# DC_unit.net
KiCad netlist of a schematic drawn in Altium Designer
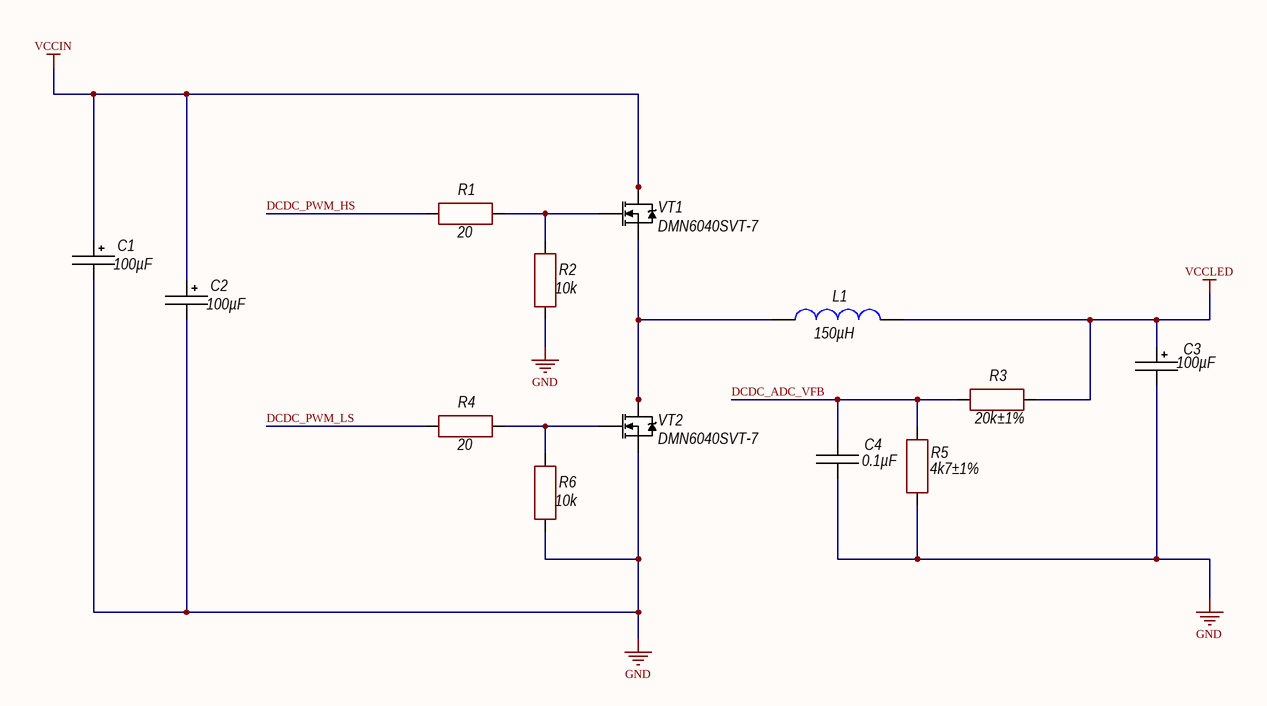
[diagram p0: DC unit.SchDoc]

(export (version "E")
  (design (tool "Eeschema 10.0.6"))
  (components
    (comp (ref "C1") (value "100µF") (footprint "D8C3.2H12") (libsource (lib "Discrete") (part "AlumCap")))
    (comp (ref "C2") (value "100µF") (footprint "D8C3.2H12") (libsource (lib "Discrete") (part "AlumCap")))
    (comp (ref "C3")
      (value "100µF")
      (footprint "TANTAL_D")
      (fields (field (name "MANUFACTURER") "Vishay Intertechnology Inc."))
      (libsource (lib "Discrete") (part "TantalCap"))
    )
    (comp (ref "C4") (value "0.1µF") (footprint "CH0603C") (libsource (lib "Discrete") (part "Capacitor")))
    (comp (ref "L1")
      (value "150µH")
      (footprint "IND: CDRH127")
      (fields (field (name "MANUFACTURER") "Sumida Electric"))
      (libsource (lib "Discrete") (part "Inductor"))
    )
    (comp (ref "R1") (value "20") (footprint "CH0603R") (libsource (lib "Discrete") (part "Resistor")))
    (comp (ref "R2") (value "10k") (footprint "CH0603R") (libsource (lib "") (part "Resistor_1")))
    (comp (ref "R3")
      (value "20k")
      (footprint "CH0603R")
      (fields (field (name "COMPONENTKIND") "±1%"))
      (libsource (lib "Discrete") (part "Resistor"))
    )
    (comp (ref "R4") (value "20") (footprint "CH0603R") (libsource (lib "Discrete") (part "Resistor")))
    (comp (ref "R5")
      (value "4k7")
      (footprint "CH0603R")
      (fields (field (name "COMPONENTKIND") "±1%"))
      (libsource (lib "") (part "Resistor_1"))
    )
    (comp (ref "R6") (value "10k") (footprint "CH0603R") (libsource (lib "") (part "Resistor_1")))
    (comp (ref "VT1")
      (value "DMN6040SVT-7")
      (footprint "TSOT23-6")
      (description "Mosfet")
      (fields (field (name "MANUFACTURER") "Diodes Incorporated"))
      (libsource (lib "Transistor") (part "DMN6040SVT-7"))
    )
    (comp (ref "VT2")
      (value "DMN6040SVT-7")
      (footprint "TSOT23-6")
      (description "Mosfet")
      (fields (field (name "MANUFACTURER") "Diodes Incorporated"))
      (libsource (lib "Transistor") (part "DMN6040SVT-7"))
    )
  )
  (nets
    (net (code "1") (name "/DCDC_ADC_VFB") (class "Default")
      (node (ref "C4") (pin "1") (pinfunction "1_1") (pintype "power_in"))
      (node (ref "R3") (pin "1") (pinfunction "1_1") (pintype "passive"))
      (node (ref "R5") (pin "2") (pinfunction "2_2") (pintype "passive"))
    )
    (net (code "2") (name "/DCDC_PWM_HS") (class "Default")
      (node (ref "R1") (pin "1") (pinfunction "1_1") (pintype "passive"))
    )
    (net (code "3") (name "/DCDC_PWM_LS") (class "Default")
      (node (ref "R4") (pin "1") (pinfunction "1_1") (pintype "passive"))
    )
    (net (code "4") (name "GND") (class "Default")
      (node (ref "C1") (pin "2") (pinfunction "2_2") (pintype "power_in"))
      (node (ref "C2") (pin "2") (pinfunction "2_2") (pintype "power_in"))
      (node (ref "C3") (pin "2") (pinfunction "2_2") (pintype "power_in"))
      (node (ref "C4") (pin "2") (pinfunction "2_2") (pintype "power_in"))
      (node (ref "R2") (pin "1") (pinfunction "1_1") (pintype "passive"))
      (node (ref "R5") (pin "1") (pinfunction "1_1") (pintype "passive"))
      (node (ref "R6") (pin "1") (pinfunction "1_1") (pintype "passive"))
      (node (ref "VT2") (pin "4") (pinfunction "S_4") (pintype "passive"))
    )
    (net (code "5") (name "Net-(VT1-G)") (class "Default")
      (node (ref "R1") (pin "2") (pinfunction "2_2") (pintype "passive"))
      (node (ref "R2") (pin "2") (pinfunction "2_2") (pintype "passive"))
      (node (ref "VT1") (pin "3") (pinfunction "G_3") (pintype "passive"))
    )
    (net (code "6") (name "Net-(VT1-S)") (class "Default")
      (node (ref "L1") (pin "2") (pinfunction "2_2") (pintype "passive"))
      (node (ref "VT1") (pin "4") (pinfunction "S_4") (pintype "passive"))
      (node (ref "VT2") (pin "1") (pinfunction "D_1") (pintype "passive"))
      (node (ref "VT2") (pin "2") (pinfunction "D_2") (pintype "passive"))
      (node (ref "VT2") (pin "5") (pinfunction "D_5") (pintype "passive"))
      (node (ref "VT2") (pin "6") (pinfunction "D_6") (pintype "passive"))
    )
    (net (code "7") (name "Net-(VT2-G)") (class "Default")
      (node (ref "R4") (pin "2") (pinfunction "2_2") (pintype "passive"))
      (node (ref "R6") (pin "2") (pinfunction "2_2") (pintype "passive"))
      (node (ref "VT2") (pin "3") (pinfunction "G_3") (pintype "passive"))
    )
    (net (code "8") (name "VCCIN") (class "Default")
      (node (ref "C1") (pin "1") (pinfunction "1_1") (pintype "power_in"))
      (node (ref "C2") (pin "1") (pinfunction "1_1") (pintype "power_in"))
      (node (ref "VT1") (pin "1") (pinfunction "D_1") (pintype "passive"))
      (node (ref "VT1") (pin "2") (pinfunction "D_2") (pintype "passive"))
      (node (ref "VT1") (pin "5") (pinfunction "D_5") (pintype "passive"))
      (node (ref "VT1") (pin "6") (pinfunction "D_6") (pintype "passive"))
    )
    (net (code "9") (name "VCCLED") (class "Default")
      (node (ref "C3") (pin "1") (pinfunction "1_1") (pintype "power_in"))
      (node (ref "L1") (pin "1") (pinfunction "1_1") (pintype "passive"))
      (node (ref "R3") (pin "2") (pinfunction "2_2") (pintype "passive"))
    )
  )
)
